# SchematicLickportPCB.net
KiCad netlist of a schematic drawn in EAGLE
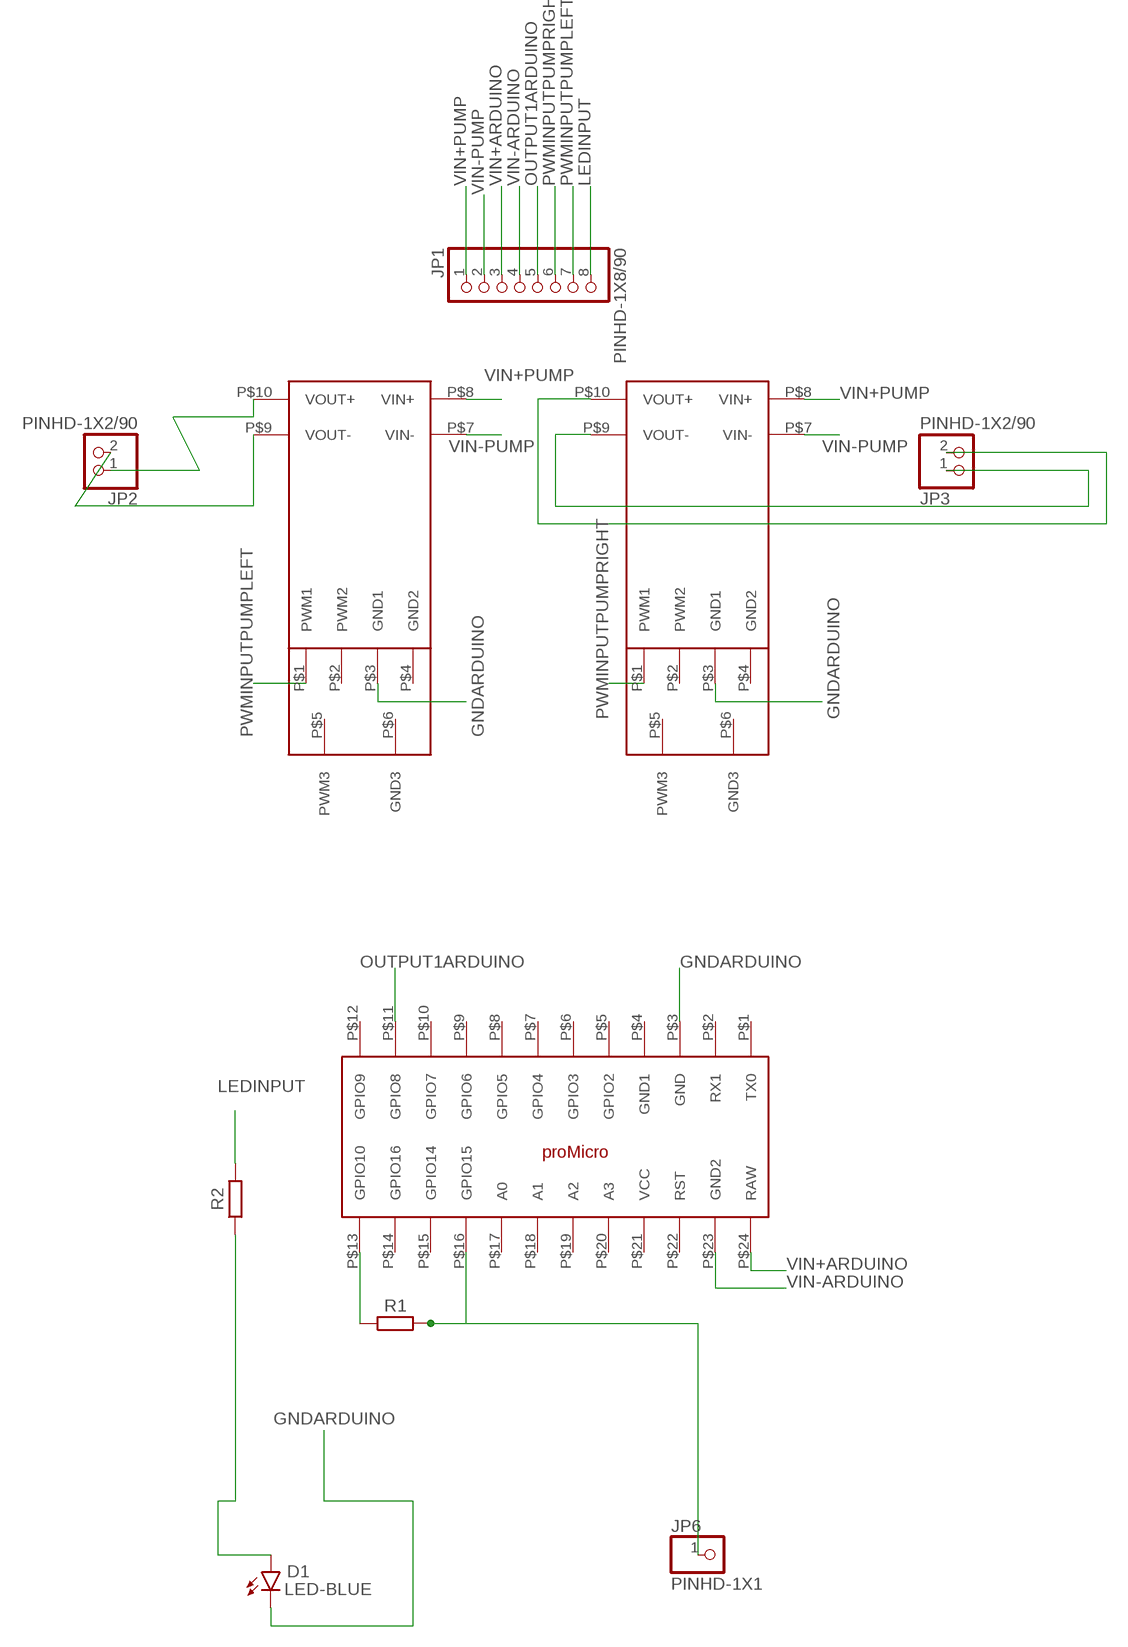
[diagram p0: schematic, sheet 1]

(export (version "E")
  (design (tool "Eeschema 10.0.6"))
  (components
    (comp (ref "D1")
      (value "LED-BLUE")
      (footprint "eagle-import:LEDRD254W60D565H860B_B")
      (libsource (lib "eagle-import") (part "LED_RADIALBLUE"))
    )
    (comp (ref "JP1")
      (value "PINHD-1X8/90")
      (footprint "eagle-import:1X08_90")
      (fields (field (name "MANUFACTURER") "Generic"))
      (libsource (lib "eagle-import") (part "PINHD-1X8/90"))
    )
    (comp (ref "JP2")
      (value "PINHD-1X2/90")
      (footprint "eagle-import:1X02_90")
      (fields (field (name "MANUFACTURER") "Generic"))
      (libsource (lib "eagle-import") (part "PINHD-1X2/90"))
    )
    (comp (ref "JP3")
      (value "PINHD-1X2/90")
      (footprint "eagle-import:1X02_90")
      (fields (field (name "MANUFACTURER") "Generic"))
      (libsource (lib "eagle-import") (part "PINHD-1X2/90"))
    )
    (comp (ref "JP6")
      (value "PINHD-1X1")
      (footprint "eagle-import:1X01")
      (fields (field (name "MANUFACTURER") "Generic"))
      (libsource (lib "eagle-import") (part "PINHD-1X1"))
    )
    (comp (ref "R1")
      (value "RESISTOR_AXIAL-11.7MM-PITCH")
      (footprint "eagle-import:RESAD1176W63L850D250B")
      (libsource (lib "eagle-import") (part "RESISTORAXIAL-11.7MM-PITCH_"))
    )
    (comp (ref "R2")
      (value "RESISTOR_AXIAL-11.7MM-PITCH")
      (footprint "eagle-import:RESAD1176W63L850D250B")
      (libsource (lib "eagle-import") (part "RESISTORAXIAL-11.7MM-PITCH_"))
    )
    (comp (ref "U$1")
      (value "MOSFET_MODULE")
      (footprint "eagle-import:MOSFET_MODULE")
      (libsource (lib "eagle-import") (part "MOSFET_MODULE"))
    )
    (comp (ref "U$2")
      (value "MOSFET_MODULE")
      (footprint "eagle-import:MOSFET_MODULE")
      (libsource (lib "eagle-import") (part "MOSFET_MODULE"))
    )
    (comp (ref "U$3")
      (value "JOY_IT_PRO_MICRO")
      (footprint "eagle-import:JOY_IT_PRO_MICRO")
      (libsource (lib "eagle-import") (part "JOY_IT_PRO_MICRO"))
    )
  )
  (nets
    (net (code "1") (name "/GNDARDUINO") (class "Default")
      (node (ref "D1") (pin "C") (pinfunction "C_C") (pintype "passive"))
      (node (ref "U$1") (pin "P$3") (pinfunction "GND1_P$3") (pintype "bidirectional"))
      (node (ref "U$2") (pin "P$3") (pinfunction "GND1_P$3") (pintype "bidirectional"))
      (node (ref "U$3") (pin "P$3") (pinfunction "GND_P$3") (pintype "bidirectional"))
    )
    (net (code "2") (name "/LEDINPUT") (class "Default")
      (node (ref "JP1") (pin "8") (pinfunction "8_8") (pintype "passive"))
      (node (ref "R2") (pin "2") (pinfunction "2_2") (pintype "passive"))
    )
    (net (code "3") (name "/OUTPUT1ARDUINO") (class "Default")
      (node (ref "JP1") (pin "5") (pinfunction "5_5") (pintype "passive"))
      (node (ref "U$3") (pin "P$11") (pinfunction "GPIO8_P$11") (pintype "bidirectional"))
    )
    (net (code "4") (name "/PWMINPUTPUMPLEFT") (class "Default")
      (node (ref "JP1") (pin "7") (pinfunction "7_7") (pintype "passive"))
      (node (ref "U$1") (pin "P$1") (pinfunction "PWM1_P$1") (pintype "bidirectional"))
    )
    (net (code "5") (name "/PWMINPUTPUMPRIGHT") (class "Default")
      (node (ref "JP1") (pin "6") (pinfunction "6_6") (pintype "passive"))
      (node (ref "U$2") (pin "P$1") (pinfunction "PWM1_P$1") (pintype "bidirectional"))
    )
    (net (code "6") (name "/VIN+ARDUINO") (class "Default")
      (node (ref "JP1") (pin "3") (pinfunction "3_3") (pintype "passive"))
      (node (ref "U$3") (pin "P$24") (pinfunction "RAW_P$24") (pintype "bidirectional"))
    )
    (net (code "7") (name "/VIN+PUMP") (class "Default")
      (node (ref "JP1") (pin "1") (pinfunction "1_1") (pintype "passive"))
      (node (ref "U$1") (pin "P$8") (pinfunction "VIN+_P$8") (pintype "bidirectional"))
      (node (ref "U$2") (pin "P$8") (pinfunction "VIN+_P$8") (pintype "bidirectional"))
    )
    (net (code "8") (name "/VIN-ARDUINO") (class "Default")
      (node (ref "JP1") (pin "4") (pinfunction "4_4") (pintype "passive"))
      (node (ref "U$3") (pin "P$23") (pinfunction "GND2_P$23") (pintype "bidirectional"))
    )
    (net (code "9") (name "/VIN-PUMP") (class "Default")
      (node (ref "JP1") (pin "2") (pinfunction "2_2") (pintype "passive"))
      (node (ref "U$1") (pin "P$7") (pinfunction "VIN-_P$7") (pintype "bidirectional"))
      (node (ref "U$2") (pin "P$7") (pinfunction "VIN-_P$7") (pintype "bidirectional"))
    )
    (net (code "10") (name "Net-(D1-PadA)") (class "Default")
      (node (ref "D1") (pin "A") (pinfunction "A_A") (pintype "passive"))
      (node (ref "R2") (pin "1") (pinfunction "1_1") (pintype "passive"))
    )
    (net (code "11") (name "Net-(U$1-VOUT+)") (class "Default")
      (node (ref "JP2") (pin "1") (pinfunction "1_1") (pintype "passive"))
      (node (ref "U$1") (pin "P$10") (pinfunction "VOUT+_P$10") (pintype "bidirectional"))
    )
    (net (code "12") (name "Net-(U$1-VOUT-)") (class "Default")
      (node (ref "JP2") (pin "2") (pinfunction "2_2") (pintype "passive"))
      (node (ref "U$1") (pin "P$9") (pinfunction "VOUT-_P$9") (pintype "bidirectional"))
    )
    (net (code "13") (name "Net-(U$2-VOUT+)") (class "Default")
      (node (ref "JP3") (pin "2") (pinfunction "2_2") (pintype "passive"))
      (node (ref "U$2") (pin "P$10") (pinfunction "VOUT+_P$10") (pintype "bidirectional"))
    )
    (net (code "14") (name "Net-(U$2-VOUT-)") (class "Default")
      (node (ref "JP3") (pin "1") (pinfunction "1_1") (pintype "passive"))
      (node (ref "U$2") (pin "P$9") (pinfunction "VOUT-_P$9") (pintype "bidirectional"))
    )
    (net (code "15") (name "Net-(U$3-GPIO10)") (class "Default")
      (node (ref "R1") (pin "1") (pinfunction "1_1") (pintype "passive"))
      (node (ref "U$3") (pin "P$13") (pinfunction "GPIO10_P$13") (pintype "bidirectional"))
    )
    (net (code "16") (name "Net-(U$3-GPIO15)") (class "Default")
      (node (ref "JP6") (pin "1") (pinfunction "1_1") (pintype "passive"))
      (node (ref "R1") (pin "2") (pinfunction "2_2") (pintype "passive"))
      (node (ref "U$3") (pin "P$16") (pinfunction "GPIO15_P$16") (pintype "bidirectional"))
    )
    (net (code "17") (name "unconnected-(U$1-GND2-PadP$4)") (class "Default")
      (node (ref "U$1") (pin "P$4") (pinfunction "GND2_P$4") (pintype "bidirectional"))
    )
    (net (code "18") (name "unconnected-(U$1-GND3-PadP$6)") (class "Default")
      (node (ref "U$1") (pin "P$6") (pinfunction "GND3_P$6") (pintype "bidirectional"))
    )
    (net (code "19") (name "unconnected-(U$1-PWM2-PadP$2)") (class "Default")
      (node (ref "U$1") (pin "P$2") (pinfunction "PWM2_P$2") (pintype "bidirectional"))
    )
    (net (code "20") (name "unconnected-(U$1-PWM3-PadP$5)") (class "Default")
      (node (ref "U$1") (pin "P$5") (pinfunction "PWM3_P$5") (pintype "bidirectional"))
    )
    (net (code "21") (name "unconnected-(U$2-GND2-PadP$4)") (class "Default")
      (node (ref "U$2") (pin "P$4") (pinfunction "GND2_P$4") (pintype "bidirectional"))
    )
    (net (code "22") (name "unconnected-(U$2-GND3-PadP$6)") (class "Default")
      (node (ref "U$2") (pin "P$6") (pinfunction "GND3_P$6") (pintype "bidirectional"))
    )
    (net (code "23") (name "unconnected-(U$2-PWM2-PadP$2)") (class "Default")
      (node (ref "U$2") (pin "P$2") (pinfunction "PWM2_P$2") (pintype "bidirectional"))
    )
    (net (code "24") (name "unconnected-(U$2-PWM3-PadP$5)") (class "Default")
      (node (ref "U$2") (pin "P$5") (pinfunction "PWM3_P$5") (pintype "bidirectional"))
    )
    (net (code "25") (name "unconnected-(U$3-A0-PadP$17)") (class "Default")
      (node (ref "U$3") (pin "P$17") (pinfunction "A0_P$17") (pintype "bidirectional"))
    )
    (net (code "26") (name "unconnected-(U$3-A1-PadP$18)") (class "Default")
      (node (ref "U$3") (pin "P$18") (pinfunction "A1_P$18") (pintype "bidirectional"))
    )
    (net (code "27") (name "unconnected-(U$3-A2-PadP$19)") (class "Default")
      (node (ref "U$3") (pin "P$19") (pinfunction "A2_P$19") (pintype "bidirectional"))
    )
    (net (code "28") (name "unconnected-(U$3-A3-PadP$20)") (class "Default")
      (node (ref "U$3") (pin "P$20") (pinfunction "A3_P$20") (pintype "bidirectional"))
    )
    (net (code "29") (name "unconnected-(U$3-GND1-PadP$4)") (class "Default")
      (node (ref "U$3") (pin "P$4") (pinfunction "GND1_P$4") (pintype "bidirectional"))
    )
    (net (code "30") (name "unconnected-(U$3-GPIO2-PadP$5)") (class "Default")
      (node (ref "U$3") (pin "P$5") (pinfunction "GPIO2_P$5") (pintype "bidirectional"))
    )
    (net (code "31") (name "unconnected-(U$3-GPIO3-PadP$6)") (class "Default")
      (node (ref "U$3") (pin "P$6") (pinfunction "GPIO3_P$6") (pintype "bidirectional"))
    )
    (net (code "32") (name "unconnected-(U$3-GPIO4-PadP$7)") (class "Default")
      (node (ref "U$3") (pin "P$7") (pinfunction "GPIO4_P$7") (pintype "bidirectional"))
    )
    (net (code "33") (name "unconnected-(U$3-GPIO5-PadP$8)") (class "Default")
      (node (ref "U$3") (pin "P$8") (pinfunction "GPIO5_P$8") (pintype "bidirectional"))
    )
    (net (code "34") (name "unconnected-(U$3-GPIO6-PadP$9)") (class "Default")
      (node (ref "U$3") (pin "P$9") (pinfunction "GPIO6_P$9") (pintype "bidirectional"))
    )
    (net (code "35") (name "unconnected-(U$3-GPIO7-PadP$10)") (class "Default")
      (node (ref "U$3") (pin "P$10") (pinfunction "GPIO7_P$10") (pintype "bidirectional"))
    )
    (net (code "36") (name "unconnected-(U$3-GPIO9-PadP$12)") (class "Default")
      (node (ref "U$3") (pin "P$12") (pinfunction "GPIO9_P$12") (pintype "bidirectional"))
    )
    (net (code "37") (name "unconnected-(U$3-GPIO14-PadP$15)") (class "Default")
      (node (ref "U$3") (pin "P$15") (pinfunction "GPIO14_P$15") (pintype "bidirectional"))
    )
    (net (code "38") (name "unconnected-(U$3-GPIO16-PadP$14)") (class "Default")
      (node (ref "U$3") (pin "P$14") (pinfunction "GPIO16_P$14") (pintype "bidirectional"))
    )
    (net (code "39") (name "unconnected-(U$3-RST-PadP$22)") (class "Default")
      (node (ref "U$3") (pin "P$22") (pinfunction "RST_P$22") (pintype "bidirectional"))
    )
    (net (code "40") (name "unconnected-(U$3-RX1-PadP$2)") (class "Default")
      (node (ref "U$3") (pin "P$2") (pinfunction "RX1_P$2") (pintype "bidirectional"))
    )
    (net (code "41") (name "unconnected-(U$3-TX0-PadP$1)") (class "Default")
      (node (ref "U$3") (pin "P$1") (pinfunction "TX0_P$1") (pintype "bidirectional"))
    )
    (net (code "42") (name "unconnected-(U$3-VCC-PadP$21)") (class "Default")
      (node (ref "U$3") (pin "P$21") (pinfunction "VCC_P$21") (pintype "bidirectional"))
    )
  )
)
